# Copy_of_LKS_0313-V1_0_1.net
KiCad netlist of a schematic drawn in Altium Designer
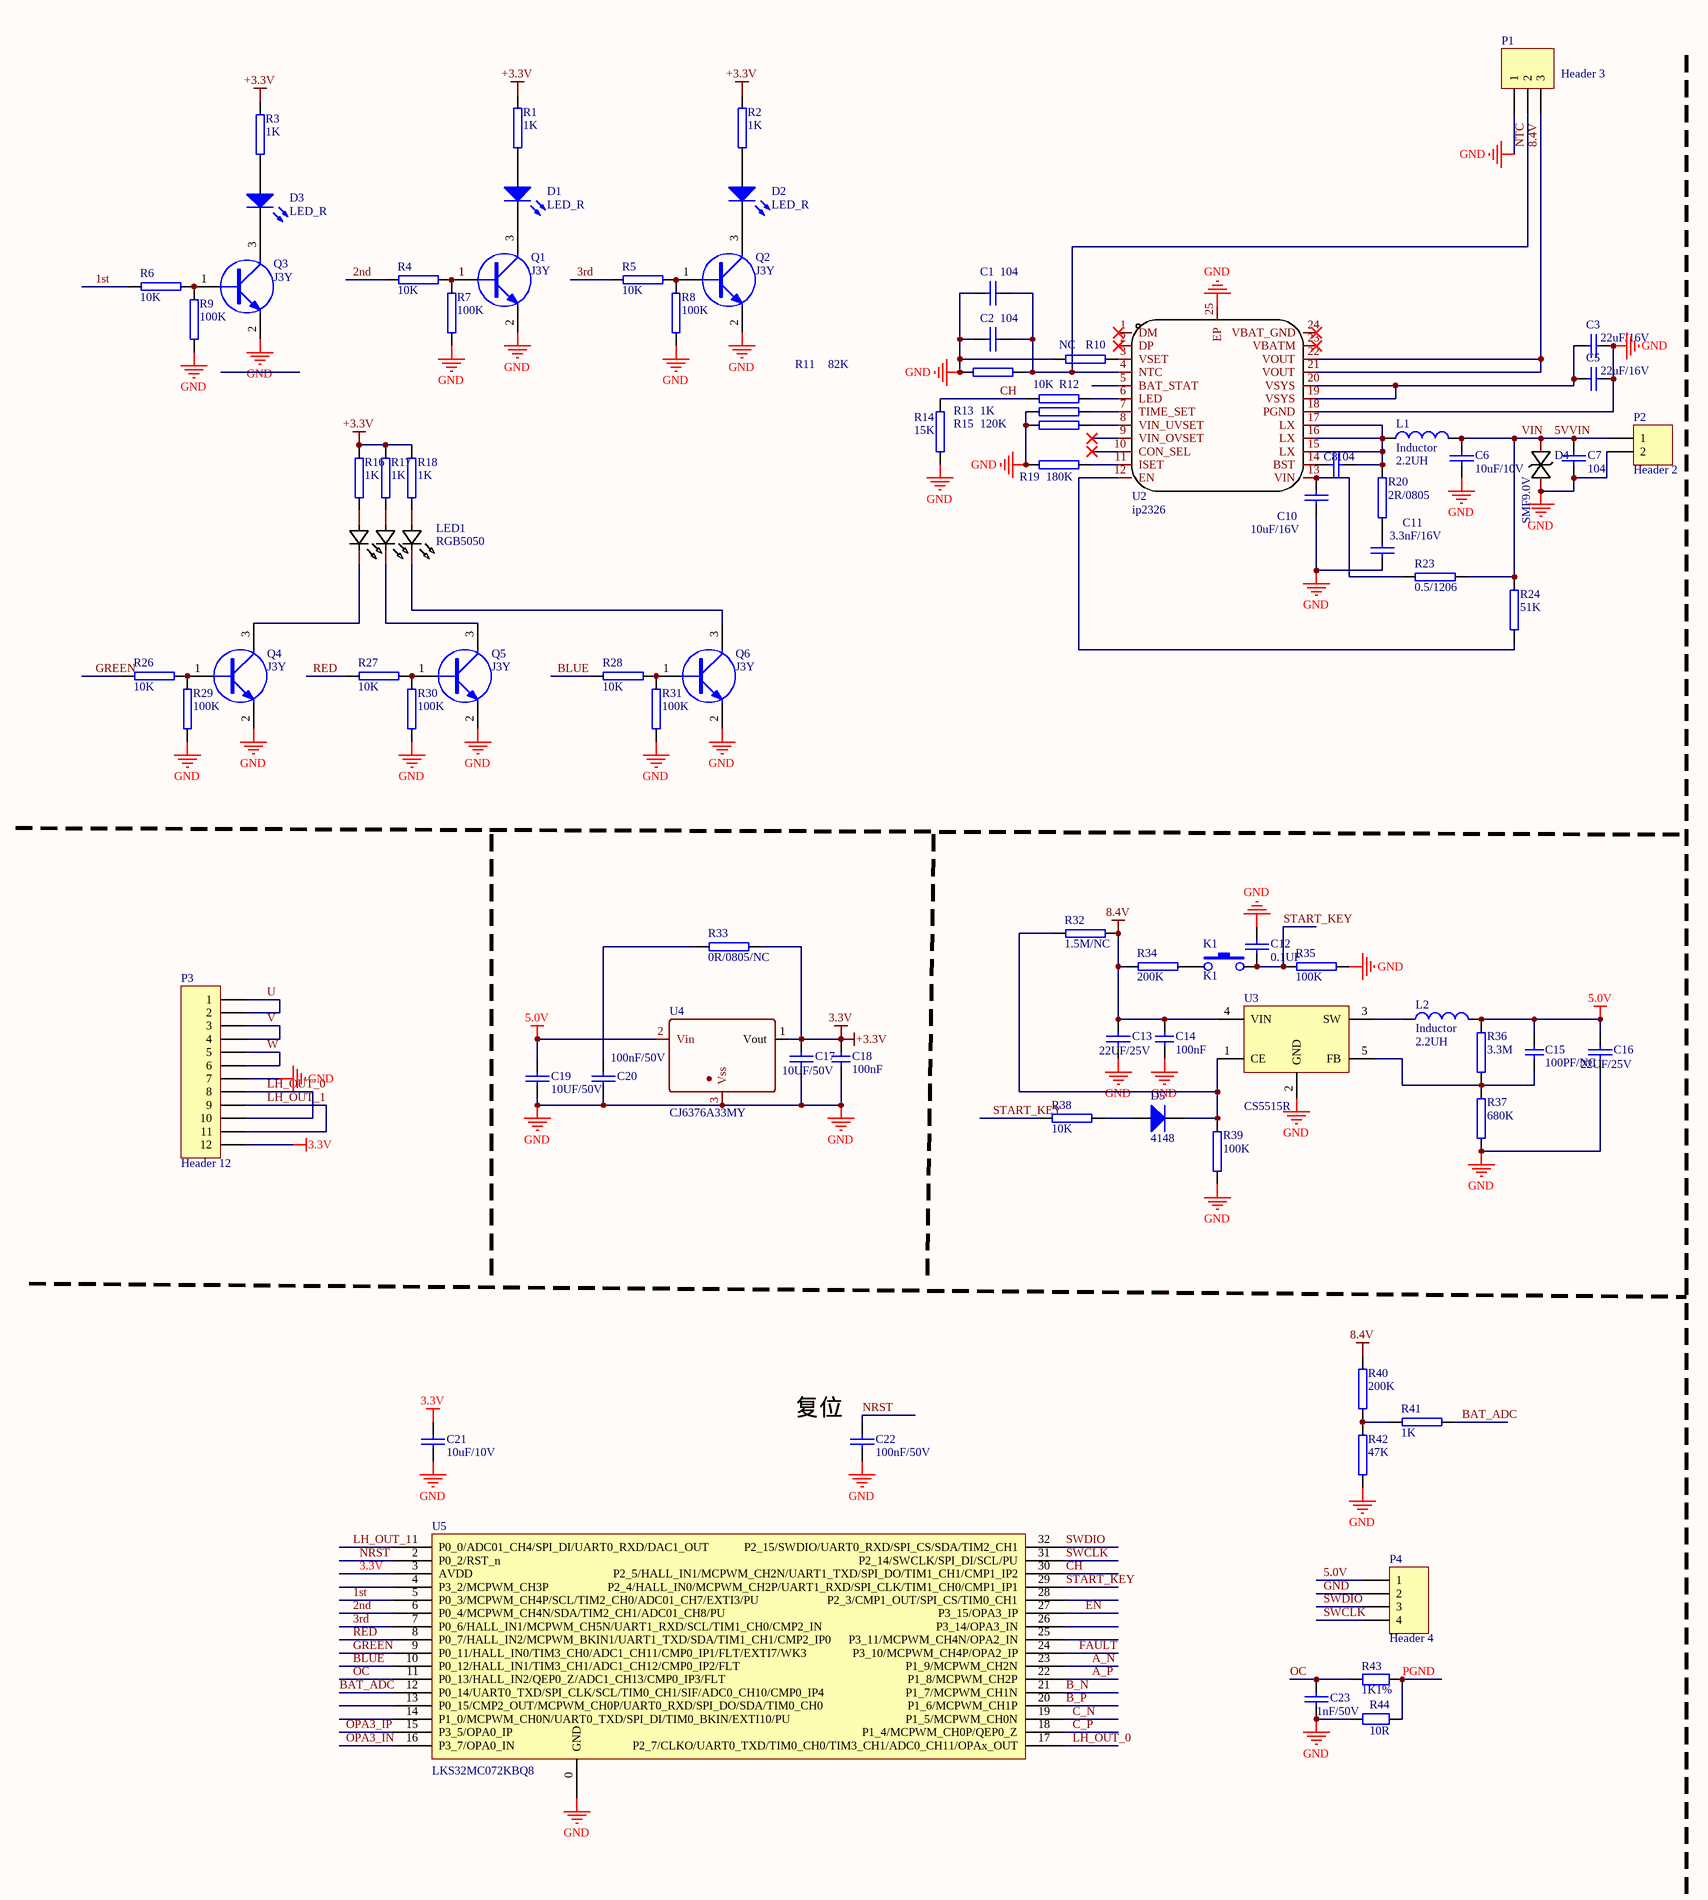
[diagram p0: Copy of LKS_0313-V1.0(1).SchDoc, left]
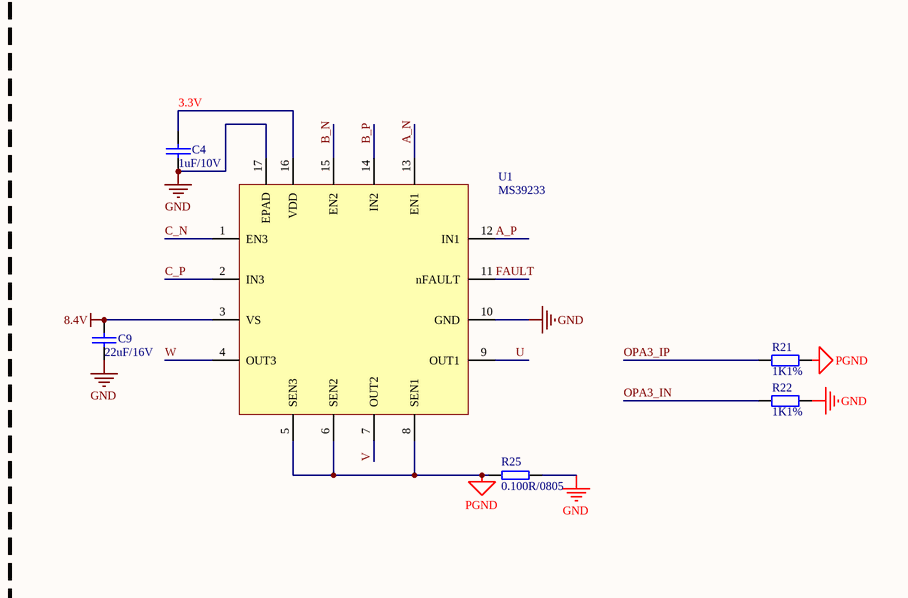
[diagram p1: Copy of LKS_0313-V1.0(1).SchDoc, right]

(export (version "E")
  (design (tool "Eeschema 10.0.6"))
  (components
    (comp (ref "C1")
      (value "104")
      (footprint "C 0402_M")
      (description "Capacitor")
      (libsource (lib "*") (part "C"))
    )
    (comp (ref "C2")
      (value "104")
      (footprint "C 0402_M")
      (description "Capacitor")
      (libsource (lib "*") (part "C"))
    )
    (comp (ref "C3")
      (value "22uF/16V")
      (footprint "C 0805_M")
      (description "Capacitor")
      (libsource (lib "*") (part "C"))
    )
    (comp (ref "C4")
      (value "1uF/10V")
      (footprint "C 0402_M")
      (description "Capacitor")
      (libsource (lib "*") (part "C"))
    )
    (comp (ref "C5")
      (value "22uF/16V")
      (footprint "C 0805_M")
      (description "Capacitor")
      (libsource (lib "*") (part "C"))
    )
    (comp (ref "C6")
      (value "10uF/10V")
      (footprint "C 0805_M")
      (description "Capacitor")
      (libsource (lib "*") (part "C"))
    )
    (comp (ref "C7")
      (value "104")
      (footprint "C 0402_M")
      (description "Capacitor")
      (libsource (lib "*") (part "C"))
    )
    (comp (ref "C8")
      (value "104")
      (footprint "C 0402_M")
      (description "Capacitor")
      (libsource (lib "*") (part "C"))
    )
    (comp (ref "C9")
      (value "22uF/16V")
      (footprint "C 0805_M")
      (description "Capacitor")
      (libsource (lib "*") (part "C"))
    )
    (comp (ref "C10")
      (value "10uF/16V")
      (footprint "C 0805_M")
      (description "Capacitor")
      (libsource (lib "*") (part "C"))
    )
    (comp (ref "C11")
      (value "3.3nF/16V")
      (footprint "C 0402_M")
      (description "Capacitor")
      (libsource (lib "*") (part "C"))
    )
    (comp (ref "C12")
      (value "0.1UF")
      (footprint "0603_RON")
      (description "Capacitor")
      (libsource (lib "STM32f401_8261_LIB") (part "CAP"))
    )
    (comp (ref "C13")
      (value "22UF/25V")
      (footprint "0805C")
      (description "Capacitor")
      (libsource (lib "*") (part "CAP"))
    )
    (comp (ref "C14") (value "100nF") (footprint "C 0402_M") (libsource (lib "") (part "CAP_1")))
    (comp (ref "C15") (value "100PF/NC") (footprint "C 0402_M") (libsource (lib "") (part "CAP_1")))
    (comp (ref "C16")
      (value "22UF/25V")
      (footprint "0805C")
      (description "Capacitor")
      (libsource (lib "*") (part "CAP"))
    )
    (comp (ref "C17")
      (value "10UF/50V")
      (footprint "0805C")
      (description "Capacitor")
      (libsource (lib "*") (part "CAP"))
    )
    (comp (ref "C18") (value "100nF") (footprint "C 0402_M") (libsource (lib "") (part "CAP_1")))
    (comp (ref "C19")
      (value "10UF/50V")
      (footprint "0805C")
      (description "Capacitor")
      (libsource (lib "*") (part "CAP"))
    )
    (comp (ref "C20")
      (value "100nF/50V")
      (footprint "C 0402_M")
      (description "Capacitor")
      (libsource (lib "*") (part "CAP"))
    )
    (comp (ref "C21")
      (value "10uF/10V")
      (footprint "0603")
      (description "Capacitor")
      (libsource (lib "*") (part "C"))
    )
    (comp (ref "C22")
      (value "100nF/50V")
      (footprint "C 0402_M")
      (description "Capacitor")
      (libsource (lib "*") (part "C"))
    )
    (comp (ref "C23")
      (value "1nF/50V")
      (footprint "C 0402_M")
      (description "Capacitor")
      (libsource (lib "*") (part "C"))
    )
    (comp (ref "D1") (value "LED_R") (footprint "SMDLED") (libsource (lib "PuXun1") (part "LED")))
    (comp (ref "D2") (value "LED_R") (footprint "SMDLED") (libsource (lib "PuXun1") (part "LED")))
    (comp (ref "D3") (value "LED_R") (footprint "SMDLED") (libsource (lib "PuXun1") (part "LED")))
    (comp (ref "D4")
      (value "SMF9.0V")
      (footprint "SOD123F")
      (libsource (lib "LKS034DO_Motor_0520_1") (part "SMF9.0V"))
    )
    (comp (ref "D5")
      (value "4148")
      (footprint "SOD-323")
      (description "Default Diode")
      (fields (field (name "PUBLISHER") "Altium Limited"))
      (libsource (lib "LKS034DO_Motor_0520_1") (part "Diode"))
    )
    (comp (ref "K1") (value "K1") (footprint "Button3x4x2") (libsource (lib "SCHLIB_NEW") (part "K1")))
    (comp (ref "L1")
      (value "Inductor")
      (footprint "0630-10UH")
      (fields (field (name "ALTIUM_VALUE") "2.2UH") (field (name "PUBLISHER") "Altium Limited"))
      (libsource (lib "Miscellaneous Devices") (part "Inductor"))
    )
    (comp (ref "L2")
      (value "Inductor")
      (footprint "0630-10UH")
      (fields (field (name "ALTIUM_VALUE") "2.2UH") (field (name "PUBLISHER") "Altium Limited"))
      (libsource (lib "Miscellaneous Devices") (part "Inductor"))
    )
    (comp (ref "LED1")
      (value "RGB5050")
      (footprint "RGB-5050")
      (libsource (lib "LKS034DO_Motor_0520_1") (part "RGB5050"))
    )
    (comp (ref "P1")
      (value "Header 3")
      (footprint "X9827WRS-3P")
      (description "Header, 3-Pin")
      (fields (field (name "PUBLISHER") "Altium Limited"))
      (libsource (lib "Miscellaneous Connectors") (part "Header 3"))
    )
    (comp (ref "P2")
      (value "Header 2")
      (footprint "X9827WRS-2P")
      (description "Header, 2-Pin")
      (fields (field (name "PUBLISHER") "Altium Limited"))
      (libsource (lib "Miscellaneous Connectors") (part "Header 2"))
    )
    (comp (ref "P3")
      (value "Header 12")
      (footprint "SMD-12")
      (description "Header, 12-Pin")
      (fields (field (name "PUBLISHER") "Altium Limited"))
      (libsource (lib "Miscellaneous Connectors") (part "Header 12"))
    )
    (comp (ref "P4")
      (value "Header 4")
      (footprint "HDR1X4")
      (description "Header, 4-Pin")
      (fields (field (name "PUBLISHER") "Altium Limited"))
      (libsource (lib "Miscellaneous Connectors") (part "Header 4"))
    )
    (comp (ref "Q1")
      (value "J3Y")
      (footprint "SOT-23")
      (description "NPN Transistor")
      (libsource (lib "*") (part "NPN"))
    )
    (comp (ref "Q2")
      (value "J3Y")
      (footprint "SOT-23")
      (description "NPN Transistor")
      (libsource (lib "*") (part "NPN"))
    )
    (comp (ref "Q3")
      (value "J3Y")
      (footprint "SOT-23")
      (description "NPN Transistor")
      (libsource (lib "*") (part "NPN"))
    )
    (comp (ref "Q4")
      (value "J3Y")
      (footprint "SOT-23")
      (description "NPN Transistor")
      (libsource (lib "*") (part "NPN"))
    )
    (comp (ref "Q5")
      (value "J3Y")
      (footprint "SOT-23")
      (description "NPN Transistor")
      (libsource (lib "*") (part "NPN"))
    )
    (comp (ref "Q6")
      (value "J3Y")
      (footprint "SOT-23")
      (description "NPN Transistor")
      (libsource (lib "*") (part "NPN"))
    )
    (comp (ref "R1") (value "1K") (footprint "C 0402_M") (libsource (lib "*") (part "RES2_S")))
    (comp (ref "R2") (value "1K") (footprint "C 0402_M") (libsource (lib "*") (part "RES2_S")))
    (comp (ref "R3") (value "1K") (footprint "C 0402_M") (libsource (lib "*") (part "RES2_S")))
    (comp (ref "R4") (value "10K") (footprint "C 0402_M") (libsource (lib "*") (part "RES2_S")))
    (comp (ref "R5") (value "10K") (footprint "C 0402_M") (libsource (lib "*") (part "RES2_S")))
    (comp (ref "R6") (value "10K") (footprint "C 0402_M") (libsource (lib "*") (part "RES2_S")))
    (comp (ref "R7") (value "100K") (footprint "C 0402_M") (libsource (lib "*") (part "RES2_S")))
    (comp (ref "R8") (value "100K") (footprint "C 0402_M") (libsource (lib "*") (part "RES2_S")))
    (comp (ref "R9") (value "100K") (footprint "C 0402_M") (libsource (lib "*") (part "RES2_S")))
    (comp (ref "R10") (value "NC") (footprint "C 0402_M") (libsource (lib "*") (part "RES2_S")))
    (comp (ref "R11") (value "82K") (footprint "C 0402_M") (libsource (lib "*") (part "RES2_S")))
    (comp (ref "R12") (value "10K") (footprint "C 0402_M") (libsource (lib "*") (part "RES2_S")))
    (comp (ref "R13") (value "1K") (footprint "C 0402_M") (libsource (lib "*") (part "RES2_S")))
    (comp (ref "R14") (value "15K") (footprint "C 0402_M") (libsource (lib "*") (part "RES2_S")))
    (comp (ref "R15") (value "120K") (footprint "C 0402_M") (libsource (lib "*") (part "RES2_S")))
    (comp (ref "R16") (value "1K") (footprint "C 0402_M") (libsource (lib "*") (part "RES2_S")))
    (comp (ref "R17") (value "1K") (footprint "C 0402_M") (libsource (lib "*") (part "RES2_S")))
    (comp (ref "R18") (value "1K") (footprint "C 0402_M") (libsource (lib "*") (part "RES2_S")))
    (comp (ref "R19") (value "180K") (footprint "C 0402_M") (libsource (lib "*") (part "RES2_S")))
    (comp (ref "R20") (value "2R/0805") (footprint "0805R") (libsource (lib "*") (part "RES2_S")))
    (comp (ref "R21")
      (value "1K1%")
      (footprint "C 0402_M")
      (description "Resistor")
      (fields (field (name "PUBLISHER") "Altium Limited"))
      (libsource (lib "LINKO_V1.0") (part "Res"))
    )
    (comp (ref "R22")
      (value "1K1%")
      (footprint "C 0402_M")
      (description "Resistor")
      (fields (field (name "PUBLISHER") "Altium Limited"))
      (libsource (lib "LINKO_V1.0") (part "Res"))
    )
    (comp (ref "R23") (value "0.5/1206") (footprint "1206R") (libsource (lib "*") (part "RES2_S")))
    (comp (ref "R24") (value "51K") (footprint "0603_RON") (libsource (lib "*") (part "RES2_S")))
    (comp (ref "R25") (value "0.100R/0805") (footprint "R 0805_M") (libsource (lib "*") (part "RES2短")))
    (comp (ref "R26") (value "10K") (footprint "C 0402_M") (libsource (lib "*") (part "RES2_S")))
    (comp (ref "R27") (value "10K") (footprint "C 0402_M") (libsource (lib "*") (part "RES2_S")))
    (comp (ref "R28") (value "10K") (footprint "C 0402_M") (libsource (lib "*") (part "RES2_S")))
    (comp (ref "R29") (value "100K") (footprint "C 0402_M") (libsource (lib "*") (part "RES2_S")))
    (comp (ref "R30") (value "100K") (footprint "C 0402_M") (libsource (lib "*") (part "RES2_S")))
    (comp (ref "R31") (value "100K") (footprint "C 0402_M") (libsource (lib "*") (part "RES2_S")))
    (comp (ref "R32") (value "1.5M/NC") (footprint "C 0402_M") (libsource (lib "*") (part "RES2_S")))
    (comp (ref "R33") (value "0R/0805/NC") (footprint "0805R") (libsource (lib "*") (part "RES2_S")))
    (comp (ref "R34") (value "200K") (footprint "C 0402_M") (libsource (lib "*") (part "RES2_S")))
    (comp (ref "R35") (value "100K") (footprint "C 0402_M") (libsource (lib "*") (part "RES2_S")))
    (comp (ref "R36") (value "3.3M") (footprint "C 0402_M") (libsource (lib "*") (part "RES2_S")))
    (comp (ref "R37") (value "680K") (footprint "0603_RON") (libsource (lib "*") (part "RES2_S")))
    (comp (ref "R38") (value "10K") (footprint "C 0402_M") (libsource (lib "*") (part "RES2_S")))
    (comp (ref "R39") (value "100K") (footprint "C 0402_M") (libsource (lib "*") (part "RES2_S")))
    (comp (ref "R40") (value "200K") (footprint "C 0402_M") (libsource (lib "*") (part "RES2_S")))
    (comp (ref "R41") (value "1K") (footprint "C 0402_M") (libsource (lib "*") (part "RES2_S")))
    (comp (ref "R42") (value "47K") (footprint "C 0402_M") (libsource (lib "*") (part "RES2_S")))
    (comp (ref "R43")
      (value "1K1%")
      (footprint "C 0402_M")
      (description "Resistor")
      (fields (field (name "PUBLISHER") "Altium Limited"))
      (libsource (lib "") (part "Res_1"))
    )
    (comp (ref "R44")
      (value "10R")
      (footprint "C 0402_M")
      (description "Resistor")
      (fields (field (name "PUBLISHER") "Altium Limited"))
      (libsource (lib "LINKO_V1.0") (part "Res"))
    )
    (comp (ref "U1") (value "MS39233") (footprint "QFN16") (libsource (lib "Schlib1") (part "MS39233")))
    (comp (ref "U2")
      (value "ip2326")
      (footprint "QFN24")
      (libsource (lib "LKS034DO_Motor_0520_1") (part "ip2326"))
    )
    (comp (ref "U3")
      (value "CS5515R")
      (footprint "SOT23-5")
      (libsource (lib "LKS034DO_Motor_0520") (part "CS5515R"))
    )
    (comp (ref "U4")
      (value "CJ6376A33MY")
      (footprint "SOT-23")
      (libsource (lib "LKS034DO_Motor_0520_1") (part "78L15"))
    )
    (comp (ref "U5")
      (value "LKS32MC072KBQ8")
      (footprint "QFN32 5x5_M")
      (description "LKS32MC072KBQ8\r\n凌鸥创芯，128KFlash，12KRAM")
      (libsource (lib "LINKO_V1.1") (part "LKS32MC072KBQ82"))
    )
  )
  (nets
    (net (code "1") (name "+3.3V") (class "Default")
      (node (ref "C17") (pin "2") (pinfunction "2_2") (pintype "passive"))
      (node (ref "C18") (pin "1") (pinfunction "1_1") (pintype "passive"))
      (node (ref "C21") (pin "2") (pinfunction "2_2") (pintype "passive"))
      (node (ref "C4") (pin "2") (pinfunction "2_2") (pintype "passive"))
      (node (ref "P3") (pin "12") (pinfunction "12_12") (pintype "passive"))
      (node (ref "R1") (pin "2") (pinfunction "2_2") (pintype "passive"))
      (node (ref "R16") (pin "2") (pinfunction "2_2") (pintype "passive"))
      (node (ref "R17") (pin "2") (pinfunction "2_2") (pintype "passive"))
      (node (ref "R18") (pin "2") (pinfunction "2_2") (pintype "passive"))
      (node (ref "R2") (pin "2") (pinfunction "2_2") (pintype "passive"))
      (node (ref "R3") (pin "2") (pinfunction "2_2") (pintype "passive"))
      (node (ref "R33") (pin "2") (pinfunction "2_2") (pintype "passive"))
      (node (ref "U1") (pin "16") (pinfunction "VDD_16") (pintype "passive"))
      (node (ref "U4") (pin "1") (pinfunction "Vout_1") (pintype "passive"))
      (node (ref "U5") (pin "3") (pinfunction "AVDD_3") (pintype "passive"))
    )
    (net (code "2") (name "/1st") (class "Default")
      (node (ref "R6") (pin "2") (pinfunction "2_2") (pintype "passive"))
      (node (ref "U5") (pin "5") (pinfunction "P0_3/MCPWM_CH4P/SCL/TIM2_CH0/ADC01_CH7/EXTI3/PU_5") (pintype "passive"))
    )
    (net (code "3") (name "/2nd") (class "Default")
      (node (ref "R4") (pin "2") (pinfunction "2_2") (pintype "passive"))
      (node (ref "U5") (pin "6") (pinfunction "P0_4/MCPWM_CH4N/SDA/TIM2_CH1/ADC01_CH8/PU_6") (pintype "passive"))
    )
    (net (code "4") (name "/3rd") (class "Default")
      (node (ref "R5") (pin "2") (pinfunction "2_2") (pintype "passive"))
      (node (ref "U5") (pin "7") (pinfunction "P0_6/HALL_IN1/MCPWM_CH5N/UART1_RXD/SCL/TIM1_CH0/CMP2_IN_7") (pintype "passive"))
    )
    (net (code "5") (name "/5VVIN") (class "Default")
      (node (ref "C6") (pin "1") (pinfunction "1_1") (pintype "passive"))
      (node (ref "C7") (pin "2") (pinfunction "2_2") (pintype "passive"))
      (node (ref "D4") (pin "2") (pinfunction "A_2") (pintype "passive"))
      (node (ref "L1") (pin "2") (pinfunction "2_2") (pintype "passive"))
      (node (ref "P2") (pin "1") (pinfunction "1_1") (pintype "passive"))
      (node (ref "R23") (pin "1") (pinfunction "1_1") (pintype "passive"))
      (node (ref "R24") (pin "1") (pinfunction "1_1") (pintype "passive"))
    )
    (net (code "6") (name "/A_N") (class "Default")
      (node (ref "U1") (pin "13") (pinfunction "EN1_13") (pintype "passive"))
      (node (ref "U5") (pin "23") (pinfunction "P1_9/MCPWM_CH2N_23") (pintype "passive"))
    )
    (net (code "7") (name "/A_P") (class "Default")
      (node (ref "U1") (pin "12") (pinfunction "IN1_12") (pintype "passive"))
      (node (ref "U5") (pin "22") (pinfunction "P1_8/MCPWM_CH2P_22") (pintype "passive"))
    )
    (net (code "8") (name "/BAT_ADC") (class "Default")
      (node (ref "R41") (pin "1") (pinfunction "1_1") (pintype "passive"))
      (node (ref "U5") (pin "12") (pinfunction "P0_14/UART0_TXD/SPI_CLK/SCL/TIM0_CH1/SIF/ADC0_CH10/CMP0_IP4_12") (pintype "passive"))
    )
    (net (code "9") (name "/BLUE") (class "Default")
      (node (ref "R28") (pin "2") (pinfunction "2_2") (pintype "passive"))
      (node (ref "U5") (pin "10") (pinfunction "P0_12/HALL_IN1/TIM3_CH1/ADC1_CH12/CMP0_IP2/FLT_10") (pintype "passive"))
    )
    (net (code "10") (name "/B_N") (class "Default")
      (node (ref "U1") (pin "15") (pinfunction "EN2_15") (pintype "passive"))
      (node (ref "U5") (pin "21") (pinfunction "P1_7/MCPWM_CH1N_21") (pintype "passive"))
    )
    (net (code "11") (name "/B_P") (class "Default")
      (node (ref "U1") (pin "14") (pinfunction "IN2_14") (pintype "passive"))
      (node (ref "U5") (pin "20") (pinfunction "P1_6/MCPWM_CH1P_20") (pintype "passive"))
    )
    (net (code "12") (name "/CH") (class "Default")
      (node (ref "R12") (pin "2") (pinfunction "2_2") (pintype "passive"))
      (node (ref "R14") (pin "1") (pinfunction "1_1") (pintype "passive"))
      (node (ref "U5") (pin "30") (pinfunction "P2_5/HALL_IN1/MCPWM_CH2N/UART1_TXD/SPI_DO/TIM1_CH1/CMP1_IP2_30") (pintype "passive"))
    )
    (net (code "13") (name "/C_N") (class "Default")
      (node (ref "U1") (pin "1") (pinfunction "EN3_1") (pintype "passive"))
      (node (ref "U5") (pin "19") (pinfunction "P1_5/MCPWM_CH0N_19") (pintype "passive"))
    )
    (net (code "14") (name "/C_P") (class "Default")
      (node (ref "U1") (pin "2") (pinfunction "IN3_2") (pintype "passive"))
      (node (ref "U5") (pin "18") (pinfunction "P1_4/MCPWM_CH0P/QEP0_Z_18") (pintype "passive"))
    )
    (net (code "15") (name "/EN") (class "Default")
      (node (ref "U5") (pin "27") (pinfunction "P3_15/OPA3_IP_27") (pintype "passive"))
    )
    (net (code "16") (name "/FAULT") (class "Default")
      (node (ref "U1") (pin "11") (pinfunction "nFAULT_11") (pintype "passive"))
      (node (ref "U5") (pin "24") (pinfunction "P3_10/MCPWM_CH4P/OPA2_IP_24") (pintype "passive"))
    )
    (net (code "17") (name "/GREEN") (class "Default")
      (node (ref "R26") (pin "2") (pinfunction "2_2") (pintype "passive"))
      (node (ref "U5") (pin "9") (pinfunction "P0_11/HALL_IN0/TIM3_CH0/ADC1_CH11/CMP0_IP1/FLT/EXTI7/WK3_9") (pintype "passive"))
    )
    (net (code "18") (name "/LH_OUT_0") (class "Default")
      (node (ref "P3") (pin "10") (pinfunction "10_10") (pintype "passive"))
      (node (ref "P3") (pin "8") (pinfunction "8_8") (pintype "passive"))
      (node (ref "U5") (pin "17") (pinfunction "P2_7/CLKO/UART0_TXD/TIM0_CH0/TIM3_CH1/ADC0_CH11/OPAx_OUT_17") (pintype "passive"))
    )
    (net (code "19") (name "/LH_OUT_1") (class "Default")
      (node (ref "P3") (pin "11") (pinfunction "11_11") (pintype "passive"))
      (node (ref "P3") (pin "9") (pinfunction "9_9") (pintype "passive"))
      (node (ref "U5") (pin "1") (pinfunction "P0_0/ADC01_CH4/SPI_DI/UART0_RXD/DAC1_OUT_1") (pintype "passive"))
    )
    (net (code "20") (name "/NRST") (class "Default")
      (node (ref "C22") (pin "1") (pinfunction "1_1") (pintype "passive"))
      (node (ref "U5") (pin "2") (pinfunction "P0_2/RST_n_2") (pintype "passive"))
    )
    (net (code "21") (name "/NTC") (class "Default")
      (node (ref "C1") (pin "1") (pinfunction "1_1") (pintype "passive"))
      (node (ref "C2") (pin "1") (pinfunction "1_1") (pintype "passive"))
      (node (ref "P1") (pin "2") (pinfunction "2_2") (pintype "passive"))
      (node (ref "R11") (pin "1") (pinfunction "1_1") (pintype "passive"))
      (node (ref "U2") (pin "4") (pinfunction "NTC_4") (pintype "passive"))
    )
    (net (code "22") (name "/OC") (class "Default")
      (node (ref "C23") (pin "2") (pinfunction "2_2") (pintype "passive"))
      (node (ref "R43") (pin "1") (pinfunction "1_1") (pintype "passive"))
      (node (ref "U5") (pin "11") (pinfunction "P0_13/HALL_IN2/QEP0_Z/ADC1_CH13/CMP0_IP3/FLT_11") (pintype "passive"))
    )
    (net (code "23") (name "/OPA3_IN") (class "Default")
      (node (ref "R22") (pin "2") (pinfunction "2_2") (pintype "passive"))
      (node (ref "U5") (pin "16") (pinfunction "P3_7/OPA0_IN_16") (pintype "passive"))
    )
    (net (code "24") (name "/OPA3_IP") (class "Default")
      (node (ref "R21") (pin "2") (pinfunction "2_2") (pintype "passive"))
      (node (ref "U5") (pin "15") (pinfunction "P3_5/OPA0_IP_15") (pintype "passive"))
    )
    (net (code "25") (name "/RED") (class "Default")
      (node (ref "R27") (pin "2") (pinfunction "2_2") (pintype "passive"))
      (node (ref "U5") (pin "8") (pinfunction "P0_7/HALL_IN2/MCPWM_BKIN1/UART1_TXD/SDA/TIM1_CH1/CMP2_IP0_8") (pintype "passive"))
    )
    (net (code "26") (name "/START_KEY") (class "Default")
      (node (ref "C12") (pin "1") (pinfunction "1_1") (pintype "passive"))
      (node (ref "K1") (pin "2") (pintype "passive"))
      (node (ref "R35") (pin "2") (pinfunction "2_2") (pintype "passive"))
      (node (ref "R38") (pin "2") (pinfunction "2_2") (pintype "passive"))
      (node (ref "U5") (pin "29") (pinfunction "P2_4/HALL_IN0/MCPWM_CH2P/UART1_RXD/SPI_CLK/TIM1_CH0/CMP1_IP1_29") (pintype "passive"))
    )
    (net (code "27") (name "/SWCLK") (class "Default")
      (node (ref "P4") (pin "4") (pinfunction "4_4") (pintype "passive"))
      (node (ref "U5") (pin "31") (pinfunction "P2_14/SWCLK/SPI_DI/SCL/PU_31") (pintype "passive"))
    )
    (net (code "28") (name "/SWDIO") (class "Default")
      (node (ref "P4") (pin "3") (pinfunction "3_3") (pintype "passive"))
      (node (ref "U5") (pin "32") (pinfunction "P2_15/SWDIO/UART0_RXD/SPI_CS/SDA/TIM2_CH1_32") (pintype "passive"))
    )
    (net (code "29") (name "/U") (class "Default")
      (node (ref "P3") (pin "1") (pinfunction "1_1") (pintype "passive"))
      (node (ref "P3") (pin "2") (pinfunction "2_2") (pintype "passive"))
      (node (ref "U1") (pin "9") (pinfunction "OUT1_9") (pintype "passive"))
    )
    (net (code "30") (name "/V") (class "Default")
      (node (ref "P3") (pin "3") (pinfunction "3_3") (pintype "passive"))
      (node (ref "P3") (pin "4") (pinfunction "4_4") (pintype "passive"))
      (node (ref "U1") (pin "7") (pinfunction "OUT2_7") (pintype "passive"))
    )
    (net (code "31") (name "/W") (class "Default")
      (node (ref "P3") (pin "5") (pinfunction "5_5") (pintype "passive"))
      (node (ref "P3") (pin "6") (pinfunction "6_6") (pintype "passive"))
      (node (ref "U1") (pin "4") (pinfunction "OUT3_4") (pintype "passive"))
    )
    (net (code "32") (name "5.0V") (class "Default")
      (node (ref "C15") (pin "1") (pinfunction "1_1") (pintype "passive"))
      (node (ref "C16") (pin "2") (pinfunction "2_2") (pintype "passive"))
      (node (ref "C19") (pin "2") (pinfunction "2_2") (pintype "passive"))
      (node (ref "L2") (pin "2") (pinfunction "2_2") (pintype "passive"))
      (node (ref "P4") (pin "1") (pinfunction "1_1") (pintype "passive"))
      (node (ref "R36") (pin "1") (pinfunction "1_1") (pintype "passive"))
      (node (ref "U4") (pin "2") (pinfunction "Vin_2") (pintype "passive"))
    )
    (net (code "33") (name "8.4V") (class "Default")
      (node (ref "C13") (pin "2") (pinfunction "2_2") (pintype "passive"))
      (node (ref "C14") (pin "1") (pinfunction "1_1") (pintype "passive"))
      (node (ref "C9") (pin "2") (pinfunction "2_2") (pintype "passive"))
      (node (ref "P1") (pin "3") (pinfunction "3_3") (pintype "passive"))
      (node (ref "R32") (pin "1") (pinfunction "1_1") (pintype "passive"))
      (node (ref "R34") (pin "2") (pinfunction "2_2") (pintype "passive"))
      (node (ref "R40") (pin "1") (pinfunction "1_1") (pintype "passive"))
      (node (ref "U1") (pin "3") (pinfunction "VS_3") (pintype "passive"))
      (node (ref "U2") (pin "21") (pinfunction "VOUT_21") (pintype "passive"))
      (node (ref "U2") (pin "22") (pinfunction "VOUT_22") (pintype "passive"))
      (node (ref "U3") (pin "4") (pinfunction "VIN_4") (pintype "passive"))
    )
    (net (code "34") (name "GND") (class "Default")
      (node (ref "C1") (pin "2") (pinfunction "2_2") (pintype "passive"))
      (node (ref "C10") (pin "2") (pinfunction "2_2") (pintype "passive"))
      (node (ref "C11") (pin "2") (pinfunction "2_2") (pintype "passive"))
      (node (ref "C12") (pin "2") (pinfunction "2_2") (pintype "passive"))
      (node (ref "C13") (pin "1") (pinfunction "1_1") (pintype "passive"))
      (node (ref "C14") (pin "2") (pinfunction "2_2") (pintype "passive"))
      (node (ref "C16") (pin "1") (pinfunction "1_1") (pintype "passive"))
      (node (ref "C17") (pin "1") (pinfunction "1_1") (pintype "passive"))
      (node (ref "C18") (pin "2") (pinfunction "2_2") (pintype "passive"))
      (node (ref "C19") (pin "1") (pinfunction "1_1") (pintype "passive"))
      (node (ref "C2") (pin "2") (pinfunction "2_2") (pintype "passive"))
      (node (ref "C20") (pin "2") (pinfunction "2_2") (pintype "passive"))
      (node (ref "C21") (pin "1") (pinfunction "1_1") (pintype "passive"))
      (node (ref "C22") (pin "2") (pinfunction "2_2") (pintype "passive"))
      (node (ref "C23") (pin "1") (pinfunction "1_1") (pintype "passive"))
      (node (ref "C3") (pin "1") (pinfunction "1_1") (pintype "passive"))
      (node (ref "C4") (pin "1") (pinfunction "1_1") (pintype "passive"))
      (node (ref "C5") (pin "1") (pinfunction "1_1") (pintype "passive"))
      (node (ref "C6") (pin "2") (pinfunction "2_2") (pintype "passive"))
      (node (ref "C7") (pin "1") (pinfunction "1_1") (pintype "passive"))
      (node (ref "C9") (pin "1") (pinfunction "1_1") (pintype "passive"))
      (node (ref "D4") (pin "1") (pinfunction "C_1") (pintype "passive"))
      (node (ref "P1") (pin "1") (pinfunction "1_1") (pintype "passive"))
      (node (ref "P2") (pin "2") (pinfunction "2_2") (pintype "passive"))
      (node (ref "P3") (pin "7") (pinfunction "7_7") (pintype "passive"))
      (node (ref "P4") (pin "2") (pinfunction "2_2") (pintype "passive"))
      (node (ref "Q1") (pin "2") (pinfunction "E_2") (pintype "passive"))
      (node (ref "Q2") (pin "2") (pinfunction "E_2") (pintype "passive"))
      (node (ref "Q3") (pin "2") (pinfunction "E_2") (pintype "passive"))
      (node (ref "Q4") (pin "2") (pinfunction "E_2") (pintype "passive"))
      (node (ref "Q5") (pin "2") (pinfunction "E_2") (pintype "passive"))
      (node (ref "Q6") (pin "2") (pinfunction "E_2") (pintype "passive"))
      (node (ref "R10") (pin "2") (pinfunction "2_2") (pintype "passive"))
      (node (ref "R11") (pin "2") (pinfunction "2_2") (pintype "passive"))
      (node (ref "R13") (pin "2") (pinfunction "2_2") (pintype "passive"))
      (node (ref "R14") (pin "2") (pinfunction "2_2") (pintype "passive"))
      (node (ref "R15") (pin "2") (pinfunction "2_2") (pintype "passive"))
      (node (ref "R19") (pin "2") (pinfunction "2_2") (pintype "passive"))
      (node (ref "R22") (pin "1") (pinfunction "1_1") (pintype "passive"))
      (node (ref "R25") (pin "2") (pinfunction "2_2") (pintype "passive"))
      (node (ref "R29") (pin "2") (pinfunction "2_2") (pintype "passive"))
      (node (ref "R30") (pin "2") (pinfunction "2_2") (pintype "passive"))
      (node (ref "R31") (pin "2") (pinfunction "2_2") (pintype "passive"))
      (node (ref "R35") (pin "1") (pinfunction "1_1") (pintype "passive"))
      (node (ref "R37") (pin "2") (pinfunction "2_2") (pintype "passive"))
      (node (ref "R39") (pin "1") (pinfunction "1_1") (pintype "passive"))
      (node (ref "R42") (pin "2") (pinfunction "2_2") (pintype "passive"))
      (node (ref "R44") (pin "2") (pinfunction "2_2") (pintype "passive"))
      (node (ref "R7") (pin "2") (pinfunction "2_2") (pintype "passive"))
      (node (ref "R8") (pin "2") (pinfunction "2_2") (pintype "passive"))
      (node (ref "R9") (pin "2") (pinfunction "2_2") (pintype "passive"))
      (node (ref "U1") (pin "10") (pinfunction "GND_10") (pintype "passive"))
      (node (ref "U1") (pin "17") (pinfunction "EPAD_17") (pintype "passive"))
      (node (ref "U2") (pin "18") (pinfunction "PGND_18") (pintype "passive"))
      (node (ref "U2") (pin "25") (pinfunction "EP_25") (pintype "passive"))
      (node (ref "U3") (pin "2") (pinfunction "GND_2") (pintype "passive"))
      (node (ref "U4") (pin "3") (pinfunction "Vss_3") (pintype "passive"))
      (node (ref "U5") (pin "0") (pinfunction "GND_0") (pintype "passive"))
    )
    (net (code "35") (name "Net-(C3-Pad2)") (class "Default")
      (node (ref "C3") (pin "2") (pinfunction "2_2") (pintype "passive"))
      (node (ref "C5") (pin "2") (pinfunction "2_2") (pintype "passive"))
      (node (ref "U2") (pin "19") (pinfunction "VSYS_19") (pintype "passive"))
      (node (ref "U2") (pin "20") (pinfunction "VSYS_20") (pintype "passive"))
    )
    (net (code "36") (name "Net-(C8-Pad2)") (class "Default")
      (node (ref "C8") (pin "2") (pinfunction "2_2") (pintype "passive"))
      (node (ref "L1") (pin "1") (pinfunction "1_1") (pintype "passive"))
      (node (ref "R20") (pin "1") (pinfunction "1_1") (pintype "passive"))
      (node (ref "U2") (pin "15") (pinfunction "LX_15") (pintype "passive"))
      (node (ref "U2") (pin "16") (pinfunction "LX_16") (pintype "passive"))
      (node (ref "U2") (pin "17") (pinfunction "LX_17") (pintype "passive"))
    )
    (net (code "37") (name "Net-(C11-Pad1)") (class "Default")
      (node (ref "C11") (pin "1") (pinfunction "1_1") (pintype "passive"))
      (node (ref "R20") (pin "2") (pinfunction "2_2") (pintype "passive"))
    )
    (net (code "38") (name "Net-(C20-Pad1)") (class "Default")
      (node (ref "C20") (pin "1") (pinfunction "1_1") (pintype "passive"))
      (node (ref "R33") (pin "1") (pinfunction "1_1") (pintype "passive"))
    )
    (net (code "39") (name "Net-(D1-A)") (class "Default")
      (node (ref "D1") (pin "1") (pinfunction "A_1") (pintype "passive"))
      (node (ref "R1") (pin "1") (pinfunction "1_1") (pintype "passive"))
    )
    (net (code "40") (name "Net-(D1-K)") (class "Default")
      (node (ref "D1") (pin "2") (pinfunction "K_2") (pintype "passive"))
      (node (ref "Q1") (pin "3") (pinfunction "C_3") (pintype "passive"))
    )
    (net (code "41") (name "Net-(D2-A)") (class "Default")
      (node (ref "D2") (pin "1") (pinfunction "A_1") (pintype "passive"))
      (node (ref "R2") (pin "1") (pinfunction "1_1") (pintype "passive"))
    )
    (net (code "42") (name "Net-(D2-K)") (class "Default")
      (node (ref "D2") (pin "2") (pinfunction "K_2") (pintype "passive"))
      (node (ref "Q2") (pin "3") (pinfunction "C_3") (pintype "passive"))
    )
    (net (code "43") (name "Net-(D3-A)") (class "Default")
      (node (ref "D3") (pin "1") (pinfunction "A_1") (pintype "passive"))
      (node (ref "R3") (pin "1") (pinfunction "1_1") (pintype "passive"))
    )
    (net (code "44") (name "Net-(D3-K)") (class "Default")
      (node (ref "D3") (pin "2") (pinfunction "K_2") (pintype "passive"))
      (node (ref "Q3") (pin "3") (pinfunction "C_3") (pintype "passive"))
    )
    (net (code "45") (name "Net-(D5-A)") (class "Default")
      (node (ref "D5") (pin "1") (pinfunction "A_1") (pintype "passive"))
      (node (ref "R38") (pin "1") (pinfunction "1_1") (pintype "passive"))
    )
    (net (code "46") (name "Net-(D5-K)") (class "Default")
      (node (ref "D5") (pin "2") (pinfunction "K_2") (pintype "passive"))
      (node (ref "R32") (pin "2") (pinfunction "2_2") (pintype "passive"))
      (node (ref "R39") (pin "2") (pinfunction "2_2") (pintype "passive"))
      (node (ref "U3") (pin "1") (pinfunction "CE_1") (pintype "passive"))
    )
    (net (code "47") (name "Net-(K1-Pad1)") (class "Default")
      (node (ref "K1") (pin "1") (pintype "passive"))
      (node (ref "R34") (pin "1") (pinfunction "1_1") (pintype "passive"))
    )
    (net (code "48") (name "Net-(LED1-+-Pad1)") (class "Default")
      (node (ref "LED1") (pin "1") (pinfunction "+_1") (pintype "passive"))
      (node (ref "R18") (pin "1") (pinfunction "1_1") (pintype "passive"))
    )
    (net (code "49") (name "Net-(LED1-+-Pad2)") (class "Default")
      (node (ref "LED1") (pin "2") (pinfunction "+_2") (pintype "passive"))
      (node (ref "R17") (pin "1") (pinfunction "1_1") (pintype "passive"))
    )
    (net (code "50") (name "Net-(LED1-+-Pad3)") (class "Default")
      (node (ref "LED1") (pin "3") (pinfunction "+_3") (pintype "passive"))
      (node (ref "R16") (pin "1") (pinfunction "1_1") (pintype "passive"))
    )
    (net (code "51") (name "Net-(Q1-B)") (class "Default")
      (node (ref "Q1") (pin "1") (pinfunction "B_1") (pintype "passive"))
      (node (ref "R4") (pin "1") (pinfunction "1_1") (pintype "passive"))
      (node (ref "R7") (pin "1") (pinfunction "1_1") (pintype "passive"))
    )
    (net (code "52") (name "Net-(Q2-B)") (class "Default")
      (node (ref "Q2") (pin "1") (pinfunction "B_1") (pintype "passive"))
      (node (ref "R5") (pin "1") (pinfunction "1_1") (pintype "passive"))
      (node (ref "R8") (pin "1") (pinfunction "1_1") (pintype "passive"))
    )
    (net (code "53") (name "Net-(Q3-B)") (class "Default")
      (node (ref "Q3") (pin "1") (pinfunction "B_1") (pintype "passive"))
      (node (ref "R6") (pin "1") (pinfunction "1_1") (pintype "passive"))
      (node (ref "R9") (pin "1") (pinfunction "1_1") (pintype "passive"))
    )
    (net (code "54") (name "Net-(Q4-B)") (class "Default")
      (node (ref "Q4") (pin "1") (pinfunction "B_1") (pintype "passive"))
      (node (ref "R26") (pin "1") (pinfunction "1_1") (pintype "passive"))
      (node (ref "R29") (pin "1") (pinfunction "1_1") (pintype "passive"))
    )
    (net (code "55") (name "Net-(Q4-C)") (class "Default")
      (node (ref "LED1") (pin "4") (pinfunction "-_4") (pintype "passive"))
      (node (ref "Q4") (pin "3") (pinfunction "C_3") (pintype "passive"))
    )
    (net (code "56") (name "Net-(Q5-B)") (class "Default")
      (node (ref "Q5") (pin "1") (pinfunction "B_1") (pintype "passive"))
      (node (ref "R27") (pin "1") (pinfunction "1_1") (pintype "passive"))
      (node (ref "R30") (pin "1") (pinfunction "1_1") (pintype "passive"))
    )
    (net (code "57") (name "Net-(Q5-C)") (class "Default")
      (node (ref "LED1") (pin "5") (pinfunction "-_5") (pintype "passive"))
      (node (ref "Q5") (pin "3") (pinfunction "C_3") (pintype "passive"))
    )
    (net (code "58") (name "Net-(Q6-B)") (class "Default")
      (node (ref "Q6") (pin "1") (pinfunction "B_1") (pintype "passive"))
      (node (ref "R28") (pin "1") (pinfunction "1_1") (pintype "passive"))
      (node (ref "R31") (pin "1") (pinfunction "1_1") (pintype "passive"))
    )
    (net (code "59") (name "Net-(Q6-C)") (class "Default")
      (node (ref "LED1") (pin "6") (pinfunction "-_6") (pintype "passive"))
      (node (ref "Q6") (pin "3") (pinfunction "C_3") (pintype "passive"))
    )
    (net (code "60") (name "Net-(R40-Pad2)") (class "Default")
      (node (ref "R40") (pin "2") (pinfunction "2_2") (pintype "passive"))
      (node (ref "R41") (pin "2") (pinfunction "2_2") (pintype "passive"))
      (node (ref "R42") (pin "1") (pinfunction "1_1") (pintype "passive"))
    )
    (net (code "61") (name "Net-(U2-BST)") (class "Default")
      (node (ref "C8") (pin "1") (pinfunction "1_1") (pintype "passive"))
      (node (ref "U2") (pin "14") (pinfunction "BST_14") (pintype "passive"))
    )
    (net (code "62") (name "Net-(U2-EN)") (class "Default")
      (node (ref "R24") (pin "2") (pinfunction "2_2") (pintype "passive"))
      (node (ref "U2") (pin "12") (pinfunction "EN_12") (pintype "passive"))
    )
    (net (code "63") (name "Net-(U2-ISET)") (class "Default")
      (node (ref "R19") (pin "1") (pinfunction "1_1") (pintype "passive"))
      (node (ref "U2") (pin "11") (pinfunction "ISET_11") (pintype "passive"))
    )
    (net (code "64") (name "Net-(U2-LED)") (class "Default")
      (node (ref "R12") (pin "1") (pinfunction "1_1") (pintype "passive"))
      (node (ref "U2") (pin "6") (pinfunction "LED_6") (pintype "passive"))
    )
    (net (code "65") (name "Net-(U2-TIME_SET)") (class "Default")
      (node (ref "R13") (pin "1") (pinfunction "1_1") (pintype "passive"))
      (node (ref "U2") (pin "7") (pinfunction "TIME_SET_7") (pintype "passive"))
    )
    (net (code "66") (name "Net-(U2-VIN)") (class "Default")
      (node (ref "C10") (pin "1") (pinfunction "1_1") (pintype "passive"))
      (node (ref "R23") (pin "2") (pinfunction "2_2") (pintype "passive"))
      (node (ref "U2") (pin "13") (pinfunction "VIN_13") (pintype "passive"))
    )
    (net (code "67") (name "Net-(U2-VIN_UVSET)") (class "Default")
      (node (ref "R15") (pin "1") (pinfunction "1_1") (pintype "passive"))
      (node (ref "U2") (pin "8") (pinfunction "VIN_UVSET_8") (pintype "passive"))
    )
    (net (code "68") (name "Net-(U2-VSET)") (class "Default")
      (node (ref "R10") (pin "1") (pinfunction "1_1") (pintype "passive"))
      (node (ref "U2") (pin "3") (pinfunction "VSET_3") (pintype "passive"))
    )
    (net (code "69") (name "Net-(U3-FB)") (class "Default")
      (node (ref "C15") (pin "2") (pinfunction "2_2") (pintype "passive"))
      (node (ref "R36") (pin "2") (pinfunction "2_2") (pintype "passive"))
      (node (ref "R37") (pin "1") (pinfunction "1_1") (pintype "passive"))
      (node (ref "U3") (pin "5") (pinfunction "FB_5") (pintype "passive"))
    )
    (net (code "70") (name "Net-(U3-SW)") (class "Default")
      (node (ref "L2") (pin "1") (pinfunction "1_1") (pintype "passive"))
      (node (ref "U3") (pin "3") (pinfunction "SW_3") (pintype "passive"))
    )
    (net (code "71") (name "PGND") (class "Default")
      (node (ref "R21") (pin "1") (pinfunction "1_1") (pintype "passive"))
      (node (ref "R25") (pin "1") (pinfunction "1_1") (pintype "passive"))
      (node (ref "R43") (pin "2") (pinfunction "2_2") (pintype "passive"))
      (node (ref "R44") (pin "1") (pinfunction "1_1") (pintype "passive"))
      (node (ref "U1") (pin "5") (pinfunction "SEN3_5") (pintype "passive"))
      (node (ref "U1") (pin "6") (pinfunction "SEN2_6") (pintype "passive"))
      (node (ref "U1") (pin "8") (pinfunction "SEN1_8") (pintype "passive"))
    )
    (net (code "72") (name "unconnected-(U2-BAT_STAT-Pad5)") (class "Default")
      (node (ref "U2") (pin "5") (pinfunction "BAT_STAT_5") (pintype "passive"))
    )
    (net (code "73") (name "unconnected-(U2-CON_SEL-Pad10)") (class "Default")
      (node (ref "U2") (pin "10") (pinfunction "CON_SEL_10") (pintype "passive+no_connect"))
    )
    (net (code "74") (name "unconnected-(U2-DM-Pad1)") (class "Default")
      (node (ref "U2") (pin "1") (pinfunction "DM_1") (pintype "passive+no_connect"))
    )
    (net (code "75") (name "unconnected-(U2-DP-Pad2)") (class "Default")
      (node (ref "U2") (pin "2") (pinfunction "DP_2") (pintype "passive+no_connect"))
    )
    (net (code "76") (name "unconnected-(U2-VBATM-Pad23)") (class "Default")
      (node (ref "U2") (pin "23") (pinfunction "VBATM_23") (pintype "passive+no_connect"))
    )
    (net (code "77") (name "unconnected-(U2-VBAT_GND-Pad24)") (class "Default")
      (node (ref "U2") (pin "24") (pinfunction "VBAT_GND_24") (pintype "passive+no_connect"))
    )
    (net (code "78") (name "unconnected-(U2-VIN_OVSET-Pad9)") (class "Default")
      (node (ref "U2") (pin "9") (pinfunction "VIN_OVSET_9") (pintype "passive+no_connect"))
    )
    (net (code "79") (name "unconnected-(U5-P0_15{slash}CMP2_OUT{slash}MCPWM_CH0P{slash}UART0_RXD{slash}SPI_DO{slash}SDA{slash}TIM0_CH0-Pad13)") (class "Default")
      (node (ref "U5") (pin "13") (pinfunction "P0_15/CMP2_OUT/MCPWM_CH0P/UART0_RXD/SPI_DO/SDA/TIM0_CH0_13") (pintype "passive"))
    )
    (net (code "80") (name "unconnected-(U5-P1_0{slash}MCPWM_CH0N{slash}UART0_TXD{slash}SPI_DI{slash}TIM0_BKIN{slash}EXTI10{slash}PU-Pad14)") (class "Default")
      (node (ref "U5") (pin "14") (pinfunction "P1_0/MCPWM_CH0N/UART0_TXD/SPI_DI/TIM0_BKIN/EXTI10/PU_14") (pintype "passive"))
    )
    (net (code "81") (name "unconnected-(U5-P2_3{slash}CMP1_OUT{slash}SPI_CS{slash}TIM0_CH1-Pad28)") (class "Default")
      (node (ref "U5") (pin "28") (pinfunction "P2_3/CMP1_OUT/SPI_CS/TIM0_CH1_28") (pintype "passive"))
    )
    (net (code "82") (name "unconnected-(U5-P3_2{slash}MCPWM_CH3P-Pad4)") (class "Default")
      (node (ref "U5") (pin "4") (pinfunction "P3_2/MCPWM_CH3P_4") (pintype "passive"))
    )
    (net (code "83") (name "unconnected-(U5-P3_11{slash}MCPWM_CH4N{slash}OPA2_IN-Pad25)") (class "Default")
      (node (ref "U5") (pin "25") (pinfunction "P3_11/MCPWM_CH4N/OPA2_IN_25") (pintype "passive"))
    )
    (net (code "84") (name "unconnected-(U5-P3_14{slash}OPA3_IN-Pad26)") (class "Default")
      (node (ref "U5") (pin "26") (pinfunction "P3_14/OPA3_IN_26") (pintype "passive"))
    )
  )
)
